# DifferentialToSingleOutput_V03_R00.net
KiCad netlist of a schematic drawn in Altium Designer
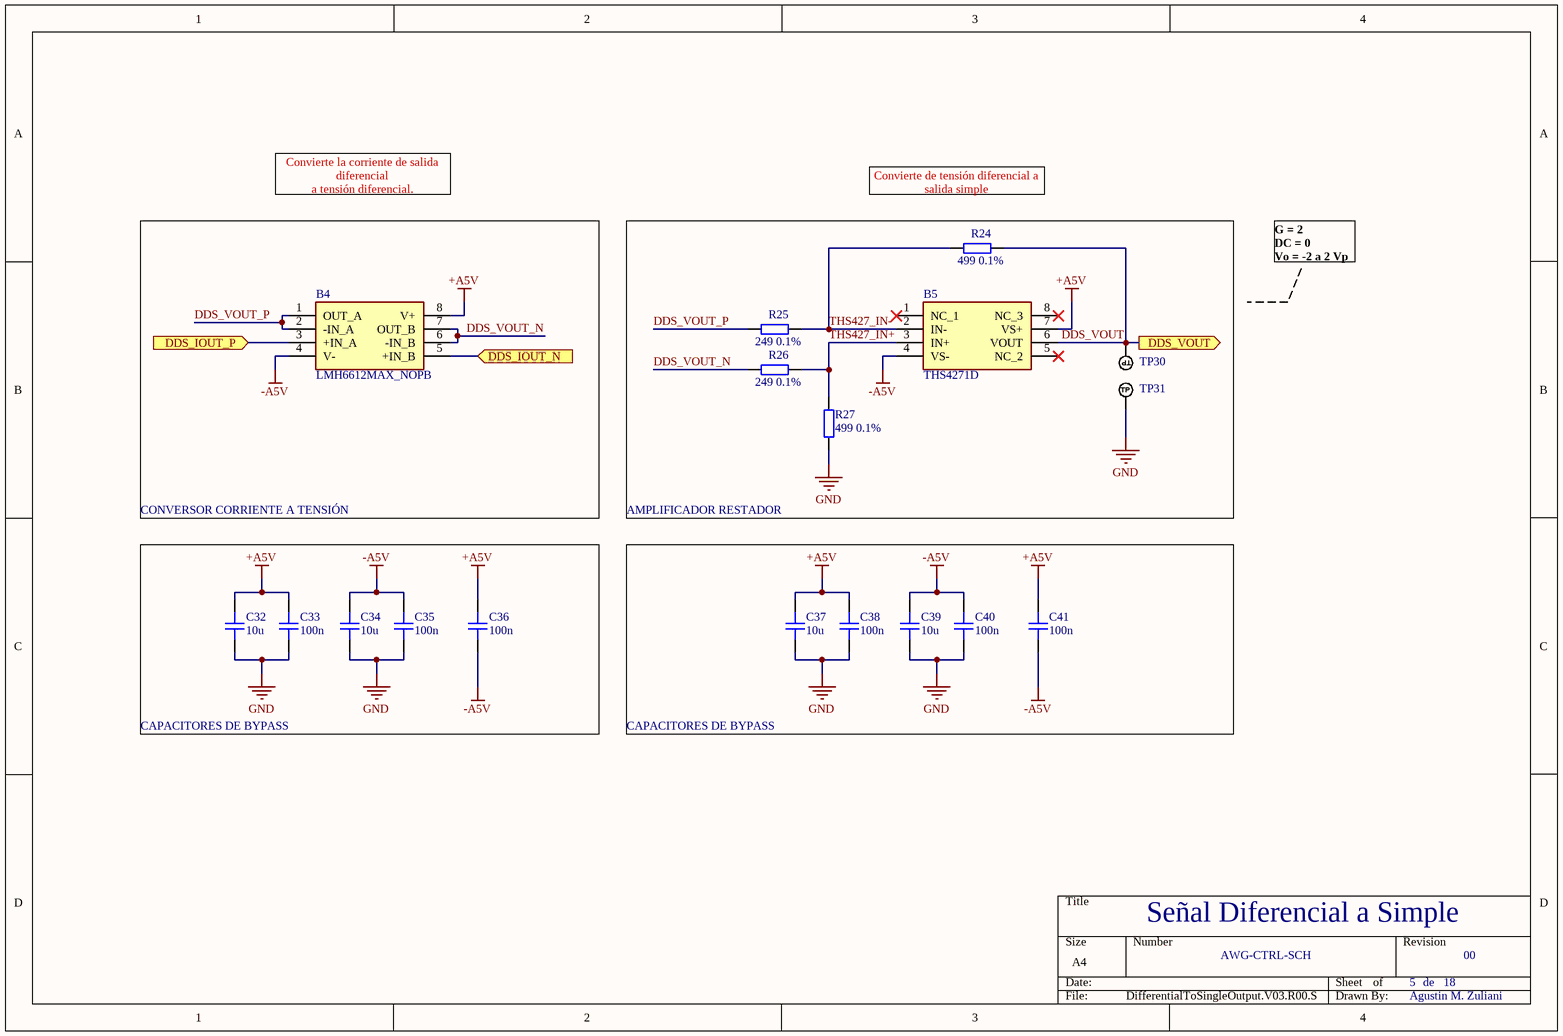
[diagram p0: DifferentialToSingleOutput.V03.R00.SchDoc]

(export (version "E")
  (design (tool "Eeschema 10.0.6"))
  (components
    (comp (ref "B4")
      (value "LMH6612MAX_NOPB")
      (footprint "SOIC127P600X175-8N")
      (description "Single Supply, Dual 345 MHz Rail-to-Rail Output Amplifier")
      (fields
        (field (name "MOUSER PART NUMBER") "926-LMH6612MAX/NOPB")
        (field (name "MANUFACTURER_PART_NUMBER") "LMH6612MAX/NOPB")
      )
      (libsource (lib "LMH6612MAX_NOPB") (part "LMH6612MAX_NOPB"))
    )
    (comp (ref "B5")
      (value "THS4271D")
      (footprint "SOIC127P600X175-8N")
      (description "Super-Fast Ultra-Low Distortion High Speed Amplifier")
      (fields (field (name "MOUSER PART NUMBER") "595-THS4271D"))
      (libsource (lib "THS4271D") (part "THS4271D"))
    )
    (comp (ref "C32")
      (value "10u")
      (footprint "CAP_0805")
      (description "Capacitor SMD 0805")
      (libsource (lib "Schematic-Lib-PhilsLab") (part "CAP_0805"))
    )
    (comp (ref "C33")
      (value "100n")
      (footprint "CAP_0805")
      (description "Capacitor SMD 0805")
      (libsource (lib "Schematic-Lib-PhilsLab") (part "CAP_0805"))
    )
    (comp (ref "C34")
      (value "10u")
      (footprint "CAP_0805")
      (description "Capacitor SMD 0805")
      (libsource (lib "Schematic-Lib-PhilsLab") (part "CAP_0805"))
    )
    (comp (ref "C35")
      (value "100n")
      (footprint "CAP_0805")
      (description "Capacitor SMD 0805")
      (libsource (lib "Schematic-Lib-PhilsLab") (part "CAP_0805"))
    )
    (comp (ref "C36")
      (value "100n")
      (footprint "CAP_0805")
      (description "Capacitor SMD 0805")
      (libsource (lib "Schematic-Lib-PhilsLab") (part "CAP_0805"))
    )
    (comp (ref "C37")
      (value "10u")
      (footprint "CAP_0805")
      (description "Capacitor SMD 0805")
      (libsource (lib "Schematic-Lib-PhilsLab") (part "CAP_0805"))
    )
    (comp (ref "C38")
      (value "100n")
      (footprint "CAP_0805")
      (description "Capacitor SMD 0805")
      (libsource (lib "Schematic-Lib-PhilsLab") (part "CAP_0805"))
    )
    (comp (ref "C39")
      (value "10u")
      (footprint "CAP_0805")
      (description "Capacitor SMD 0805")
      (libsource (lib "Schematic-Lib-PhilsLab") (part "CAP_0805"))
    )
    (comp (ref "C40")
      (value "100n")
      (footprint "CAP_0805")
      (description "Capacitor SMD 0805")
      (libsource (lib "Schematic-Lib-PhilsLab") (part "CAP_0805"))
    )
    (comp (ref "C41")
      (value "100n")
      (footprint "CAP_0805")
      (description "Capacitor SMD 0805")
      (libsource (lib "Schematic-Lib-PhilsLab") (part "CAP_0805"))
    )
    (comp (ref "R24")
      (value "499 0.1%")
      (footprint "RES_0805")
      (description "Resistor SMD 0805")
      (libsource (lib "Schematic-Lib-PhilsLab") (part "RES_0805"))
    )
    (comp (ref "R25")
      (value "249 0.1%")
      (footprint "RES_0805")
      (description "Resistor SMD 0805")
      (libsource (lib "Schematic-Lib-PhilsLab") (part "RES_0805"))
    )
    (comp (ref "R26")
      (value "249 0.1%")
      (footprint "RES_0805")
      (description "Resistor SMD 0805")
      (libsource (lib "Schematic-Lib-PhilsLab") (part "RES_0805"))
    )
    (comp (ref "R27")
      (value "499 0.1%")
      (footprint "RES_0805")
      (description "Resistor SMD 0805")
      (libsource (lib "Schematic-Lib-PhilsLab") (part "RES_0805"))
    )
    (comp (ref "TP30")
      (value "TP_NOBOM")
      (footprint "PAD_RND_1MM")
      (description "Test Point Round 1mm (NO BOM)")
      (libsource (lib "Schematic-Lib-PhilsLab") (part "TEST_POINT_RND_1MM"))
    )
    (comp (ref "TP31")
      (value "TP_NOBOM")
      (footprint "PAD_RND_1MM")
      (description "Test Point Round 1mm (NO BOM)")
      (libsource (lib "Schematic-Lib-PhilsLab") (part "TEST_POINT_RND_1MM"))
    )
  )
  (nets
    (net (code "1") (name "+A5V") (class "Default")
      (node (ref "B4") (pin "8") (pinfunction "V+_8") (pintype "passive"))
      (node (ref "B5") (pin "7") (pinfunction "VS+_7") (pintype "passive"))
      (node (ref "C32") (pin "2") (pinfunction "2_2") (pintype "passive"))
      (node (ref "C33") (pin "2") (pinfunction "2_2") (pintype "passive"))
      (node (ref "C36") (pin "2") (pinfunction "2_2") (pintype "passive"))
      (node (ref "C37") (pin "2") (pinfunction "2_2") (pintype "passive"))
      (node (ref "C38") (pin "2") (pinfunction "2_2") (pintype "passive"))
      (node (ref "C41") (pin "2") (pinfunction "2_2") (pintype "passive"))
    )
    (net (code "2") (name "-A5V") (class "Default")
      (node (ref "B4") (pin "4") (pinfunction "V-_4") (pintype "passive"))
      (node (ref "B5") (pin "4") (pinfunction "VS-_4") (pintype "passive"))
      (node (ref "C34") (pin "2") (pinfunction "2_2") (pintype "passive"))
      (node (ref "C35") (pin "2") (pinfunction "2_2") (pintype "passive"))
      (node (ref "C36") (pin "1") (pinfunction "1_1") (pintype "passive"))
      (node (ref "C39") (pin "2") (pinfunction "2_2") (pintype "passive"))
      (node (ref "C40") (pin "2") (pinfunction "2_2") (pintype "passive"))
      (node (ref "C41") (pin "1") (pinfunction "1_1") (pintype "passive"))
    )
    (net (code "3") (name "/DDS_IOUT_N") (class "Default")
      (node (ref "B4") (pin "5") (pinfunction "+IN_B_5") (pintype "passive"))
    )
    (net (code "4") (name "/DDS_IOUT_P") (class "Default")
      (node (ref "B4") (pin "3") (pinfunction "+IN_A_3") (pintype "passive"))
    )
    (net (code "5") (name "/DDS_VOUT") (class "Default")
      (node (ref "B5") (pin "6") (pinfunction "VOUT_6") (pintype "passive"))
      (node (ref "R24") (pin "2") (pinfunction "2_2") (pintype "passive"))
      (node (ref "TP30") (pin "1") (pinfunction "TP_1") (pintype "passive"))
    )
    (net (code "6") (name "/DDS_VOUT_N") (class "Default")
      (node (ref "B4") (pin "6") (pinfunction "-IN_B_6") (pintype "passive"))
      (node (ref "B4") (pin "7") (pinfunction "OUT_B_7") (pintype "passive"))
      (node (ref "R26") (pin "1") (pinfunction "1_1") (pintype "passive"))
    )
    (net (code "7") (name "/DDS_VOUT_P") (class "Default")
      (node (ref "B4") (pin "1") (pinfunction "OUT_A_1") (pintype "passive"))
      (node (ref "B4") (pin "2") (pinfunction "-IN_A_2") (pintype "passive"))
      (node (ref "R25") (pin "1") (pinfunction "1_1") (pintype "passive"))
    )
    (net (code "8") (name "/THS427_IN+") (class "Default")
      (node (ref "B5") (pin "3") (pinfunction "IN+_3") (pintype "passive"))
      (node (ref "R26") (pin "2") (pinfunction "2_2") (pintype "passive"))
      (node (ref "R27") (pin "2") (pinfunction "2_2") (pintype "passive"))
    )
    (net (code "9") (name "/THS427_IN-") (class "Default")
      (node (ref "B5") (pin "2") (pinfunction "IN-_2") (pintype "passive"))
      (node (ref "R24") (pin "1") (pinfunction "1_1") (pintype "passive"))
      (node (ref "R25") (pin "2") (pinfunction "2_2") (pintype "passive"))
    )
    (net (code "10") (name "GND") (class "Default")
      (node (ref "C32") (pin "1") (pinfunction "1_1") (pintype "passive"))
      (node (ref "C33") (pin "1") (pinfunction "1_1") (pintype "passive"))
      (node (ref "C34") (pin "1") (pinfunction "1_1") (pintype "passive"))
      (node (ref "C35") (pin "1") (pinfunction "1_1") (pintype "passive"))
      (node (ref "C37") (pin "1") (pinfunction "1_1") (pintype "passive"))
      (node (ref "C38") (pin "1") (pinfunction "1_1") (pintype "passive"))
      (node (ref "C39") (pin "1") (pinfunction "1_1") (pintype "passive"))
      (node (ref "C40") (pin "1") (pinfunction "1_1") (pintype "passive"))
      (node (ref "R27") (pin "1") (pinfunction "1_1") (pintype "passive"))
      (node (ref "TP31") (pin "1") (pinfunction "TP_1") (pintype "passive"))
    )
    (net (code "11") (name "unconnected-(B5-NC_1-Pad1)") (class "Default")
      (node (ref "B5") (pin "1") (pinfunction "NC_1_1") (pintype "passive+no_connect"))
    )
    (net (code "12") (name "unconnected-(B5-NC_2-Pad5)") (class "Default")
      (node (ref "B5") (pin "5") (pinfunction "NC_2_5") (pintype "passive+no_connect"))
    )
    (net (code "13") (name "unconnected-(B5-NC_3-Pad8)") (class "Default")
      (node (ref "B5") (pin "8") (pinfunction "NC_3_8") (pintype "passive+no_connect"))
    )
  )
)
